# bubbledisplayfrontpack_v01.net
KiCad netlist of a schematic drawn in EAGLE
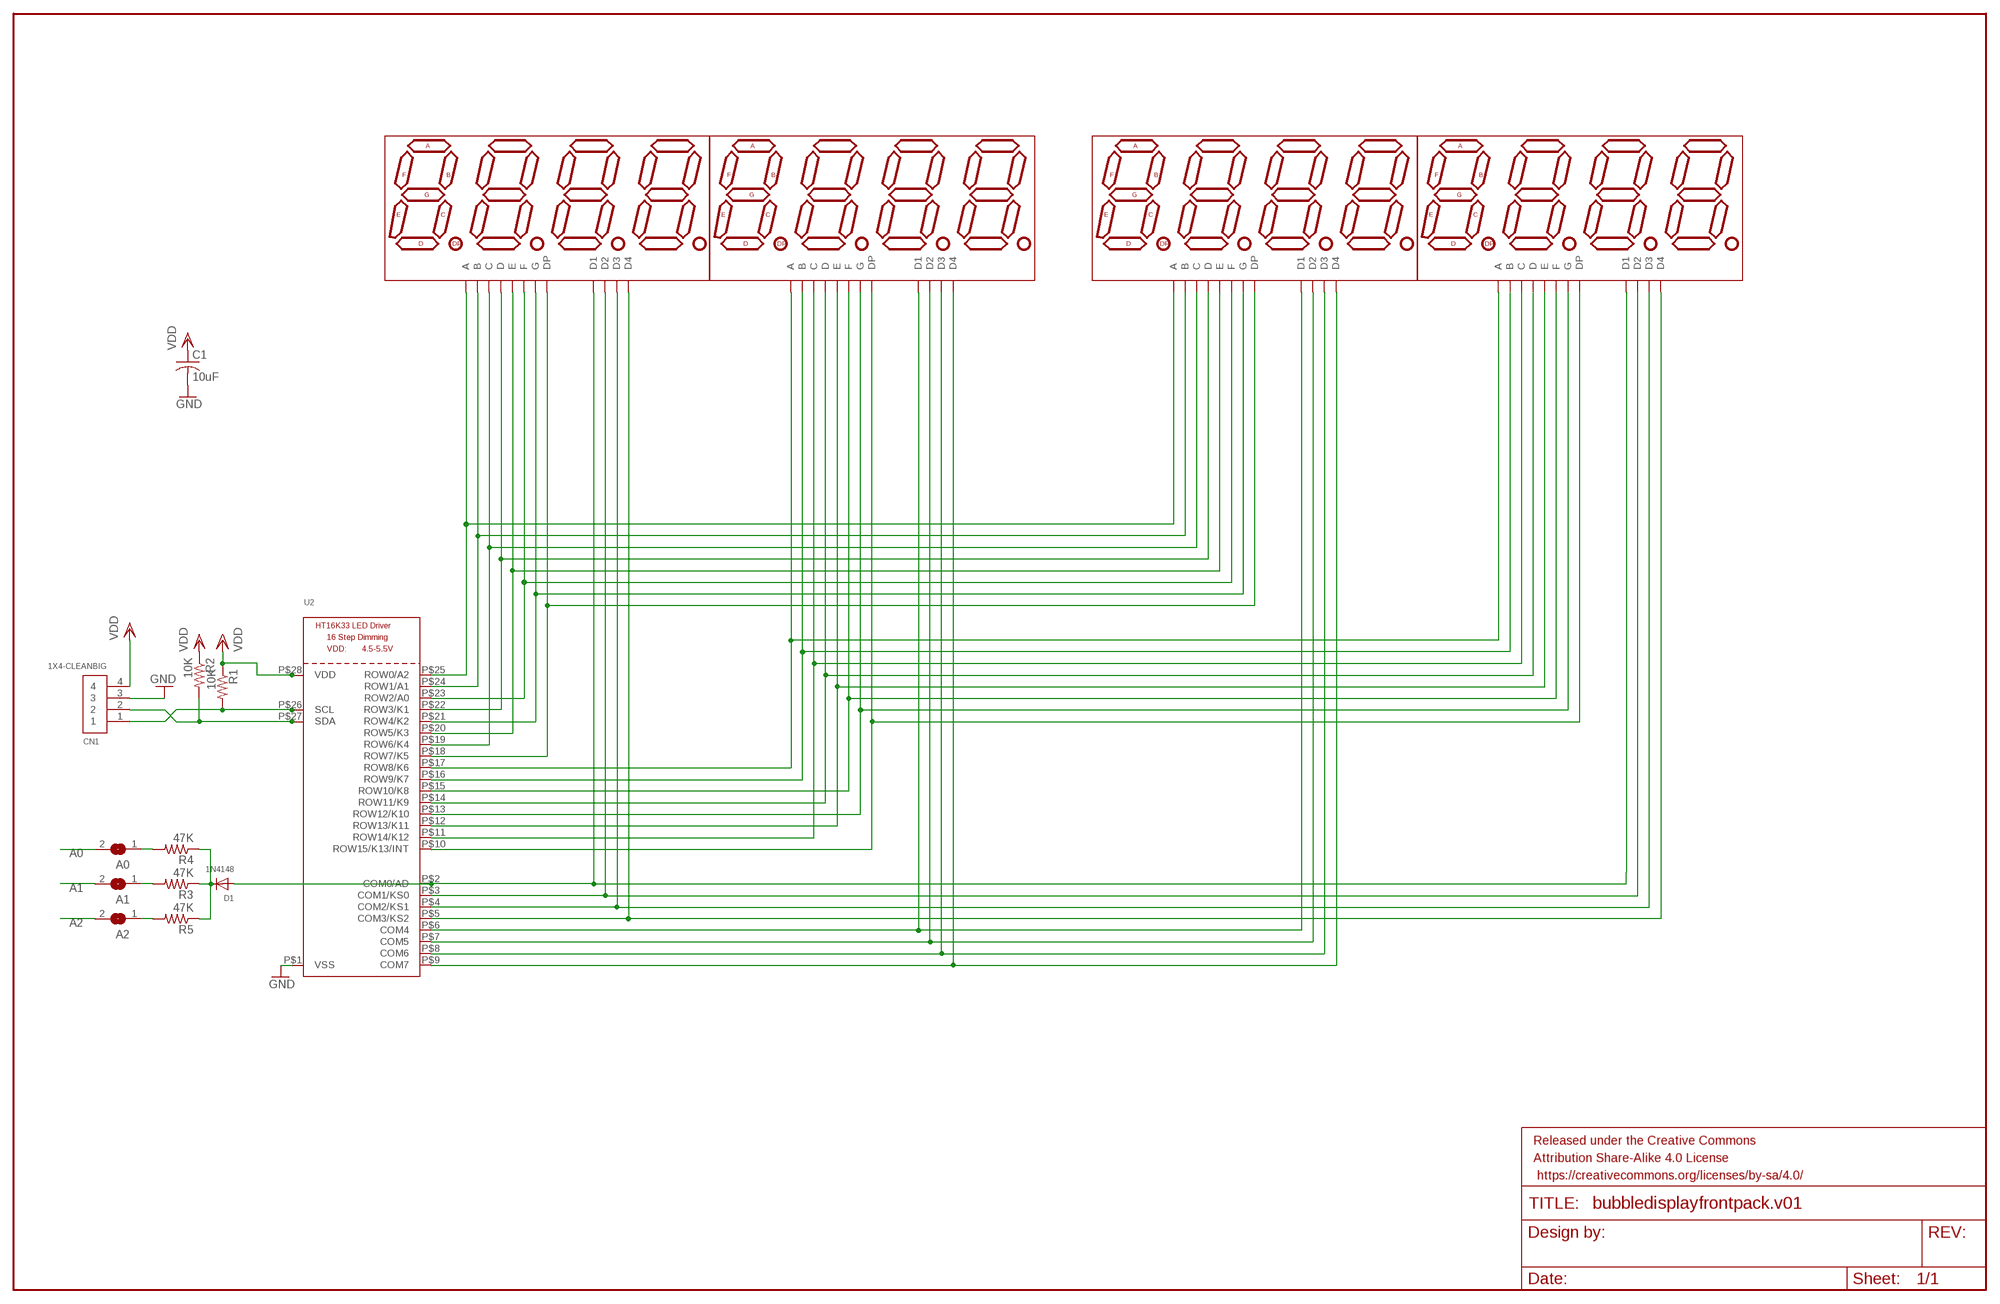
[diagram p0: schematic, sheet 1]

(export (version "E")
  (design (tool "Eeschema 10.0.6"))
  (components
    (comp (ref "A0")
      (value "SOLDERJUMPERREFLOW_NOPASTE")
      (footprint "eagle-import:SOLDERJUMPER_REFLOW_NOPASTE")
      (libsource (lib "eagle-import") (part "SOLDERJUMPERREFLOW_NOPASTE"))
    )
    (comp (ref "A1")
      (value "SOLDERJUMPERREFLOW_NOPASTE")
      (footprint "eagle-import:SOLDERJUMPER_REFLOW_NOPASTE")
      (libsource (lib "eagle-import") (part "SOLDERJUMPERREFLOW_NOPASTE"))
    )
    (comp (ref "A2")
      (value "SOLDERJUMPERREFLOW_NOPASTE")
      (footprint "eagle-import:SOLDERJUMPER_REFLOW_NOPASTE")
      (libsource (lib "eagle-import") (part "SOLDERJUMPERREFLOW_NOPASTE"))
    )
    (comp (ref "C1")
      (value "10uF")
      (footprint "eagle-import:C0805K")
      (libsource (lib "eagle-import") (part "C-USC0805K"))
    )
    (comp (ref "CN1")
      (value "1X4-CLEANBIG")
      (footprint "eagle-import:1X04-CLEANBIG")
      (libsource (lib "eagle-import") (part "1X4-CLEANBIG"))
    )
    (comp (ref "D1")
      (value "1N4148")
      (footprint "eagle-import:SOD-323F")
      (libsource (lib "eagle-import") (part "DIODESOD-323F"))
    )
    (comp (ref "DISPLAY1")
      (value "hp")
      (footprint "eagle-import:DIL12")
      (libsource (lib "eagle-import") (part "7-SEGMENT-4DIGIT-COUNTER-HP-BUBBLE"))
    )
    (comp (ref "DISPLAY2")
      (value "hp")
      (footprint "eagle-import:DIL12")
      (libsource (lib "eagle-import") (part "7-SEGMENT-4DIGIT-COUNTER-HP-BUBBLE"))
    )
    (comp (ref "DISPLAY3")
      (value "hp")
      (footprint "eagle-import:DIL12")
      (libsource (lib "eagle-import") (part "7-SEGMENT-4DIGIT-COUNTER-HP-BUBBLE"))
    )
    (comp (ref "DISPLAY4")
      (value "hp")
      (footprint "eagle-import:DIL12")
      (libsource (lib "eagle-import") (part "7-SEGMENT-4DIGIT-COUNTER-HP-BUBBLE"))
    )
    (comp (ref "FRAME1")
      (value "FRAME-LEDGER")
      (footprint "eagle-import:CREATIVE_COMMONS")
      (libsource (lib "eagle-import") (part "FRAME-LEDGER"))
    )
    (comp (ref "R1")
      (value "10K")
      (footprint "eagle-import:R0805")
      (libsource (lib "eagle-import") (part "R-US_R0805"))
    )
    (comp (ref "R2")
      (value "10K")
      (footprint "eagle-import:R0805")
      (libsource (lib "eagle-import") (part "R-US_R0805"))
    )
    (comp (ref "R3")
      (value "47K")
      (footprint "eagle-import:R0805")
      (libsource (lib "eagle-import") (part "R-US_R0805"))
    )
    (comp (ref "R4")
      (value "47K")
      (footprint "eagle-import:R0805")
      (libsource (lib "eagle-import") (part "R-US_R0805"))
    )
    (comp (ref "R5")
      (value "47K")
      (footprint "eagle-import:R0805")
      (libsource (lib "eagle-import") (part "R-US_R0805"))
    )
    (comp (ref "U2")
      (value "HT16K33_SOP28")
      (footprint "eagle-import:SOP28_300MIL")
      (libsource (lib "eagle-import") (part "HT16K33_SOP28"))
    )
  )
  (nets
    (net (code "1") (name "/A0") (class "Default")
      (node (ref "A0") (pin "2") (pinfunction "2_2") (pintype "passive"))
      (node (ref "DISPLAY1") (pin "9") (pinfunction "F_9") (pintype "bidirectional"))
      (node (ref "DISPLAY3") (pin "9") (pinfunction "F_9") (pintype "bidirectional"))
      (node (ref "U2") (pin "P$23") (pinfunction "ROW2/A0_P$23") (pintype "bidirectional"))
    )
    (net (code "2") (name "/A1") (class "Default")
      (node (ref "A1") (pin "2") (pinfunction "2_2") (pintype "passive"))
      (node (ref "DISPLAY1") (pin "11") (pinfunction "B_11") (pintype "bidirectional"))
      (node (ref "DISPLAY3") (pin "11") (pinfunction "B_11") (pintype "bidirectional"))
      (node (ref "U2") (pin "P$24") (pinfunction "ROW1/A1_P$24") (pintype "bidirectional"))
    )
    (net (code "3") (name "/A2") (class "Default")
      (node (ref "A2") (pin "2") (pinfunction "2_2") (pintype "passive"))
      (node (ref "DISPLAY1") (pin "12") (pinfunction "A_12") (pintype "bidirectional"))
      (node (ref "DISPLAY3") (pin "12") (pinfunction "A_12") (pintype "bidirectional"))
      (node (ref "U2") (pin "P$25") (pinfunction "ROW0/A2_P$25") (pintype "bidirectional"))
    )
    (net (code "4") (name "GND") (class "Default")
      (node (ref "C1") (pin "2") (pinfunction "2_2") (pintype "passive"))
      (node (ref "CN1") (pin "3") (pinfunction "3_3") (pintype "bidirectional"))
      (node (ref "U2") (pin "P$1") (pinfunction "VSS_P$1") (pintype "bidirectional"))
    )
    (net (code "5") (name "Net-(A0-Pad1)") (class "Default")
      (node (ref "A0") (pin "1") (pinfunction "1_1") (pintype "passive"))
      (node (ref "R4") (pin "2") (pinfunction "2_2") (pintype "passive"))
    )
    (net (code "6") (name "Net-(A1-Pad1)") (class "Default")
      (node (ref "A1") (pin "1") (pinfunction "1_1") (pintype "passive"))
      (node (ref "R3") (pin "2") (pinfunction "2_2") (pintype "passive"))
    )
    (net (code "7") (name "Net-(A2-Pad1)") (class "Default")
      (node (ref "A2") (pin "1") (pinfunction "1_1") (pintype "passive"))
      (node (ref "R5") (pin "2") (pinfunction "2_2") (pintype "passive"))
    )
    (net (code "8") (name "Net-(D1-PadC)") (class "Default")
      (node (ref "D1") (pin "C") (pinfunction "C_C") (pintype "passive"))
      (node (ref "R3") (pin "1") (pinfunction "1_1") (pintype "passive"))
      (node (ref "R4") (pin "1") (pinfunction "1_1") (pintype "passive"))
      (node (ref "R5") (pin "1") (pinfunction "1_1") (pintype "passive"))
    )
    (net (code "9") (name "Net-(DISPLAY1-C)") (class "Default")
      (node (ref "DISPLAY1") (pin "3") (pinfunction "C_3") (pintype "bidirectional"))
      (node (ref "DISPLAY3") (pin "3") (pinfunction "C_3") (pintype "bidirectional"))
      (node (ref "U2") (pin "P$19") (pinfunction "ROW6/K4_P$19") (pintype "bidirectional"))
    )
    (net (code "10") (name "Net-(DISPLAY1-D)") (class "Default")
      (node (ref "DISPLAY1") (pin "8") (pinfunction "D_8") (pintype "bidirectional"))
      (node (ref "DISPLAY3") (pin "8") (pinfunction "D_8") (pintype "bidirectional"))
      (node (ref "U2") (pin "P$22") (pinfunction "ROW3/K1_P$22") (pintype "bidirectional"))
    )
    (net (code "11") (name "Net-(DISPLAY1-D1)") (class "Default")
      (node (ref "DISPLAY1") (pin "1") (pinfunction "D1_1") (pintype "bidirectional"))
      (node (ref "DISPLAY4") (pin "1") (pinfunction "D1_1") (pintype "bidirectional"))
      (node (ref "U2") (pin "P$6") (pinfunction "COM4_P$6") (pintype "bidirectional"))
    )
    (net (code "12") (name "Net-(DISPLAY1-D2)") (class "Default")
      (node (ref "DISPLAY1") (pin "10") (pinfunction "D2_10") (pintype "bidirectional"))
      (node (ref "DISPLAY4") (pin "10") (pinfunction "D2_10") (pintype "bidirectional"))
      (node (ref "U2") (pin "P$7") (pinfunction "COM5_P$7") (pintype "bidirectional"))
    )
    (net (code "13") (name "Net-(DISPLAY1-D3)") (class "Default")
      (node (ref "DISPLAY1") (pin "4") (pinfunction "D3_4") (pintype "bidirectional"))
      (node (ref "DISPLAY4") (pin "4") (pinfunction "D3_4") (pintype "bidirectional"))
      (node (ref "U2") (pin "P$8") (pinfunction "COM6_P$8") (pintype "bidirectional"))
    )
    (net (code "14") (name "Net-(DISPLAY1-D4)") (class "Default")
      (node (ref "DISPLAY1") (pin "6") (pinfunction "D4_6") (pintype "bidirectional"))
      (node (ref "DISPLAY4") (pin "6") (pinfunction "D4_6") (pintype "bidirectional"))
      (node (ref "U2") (pin "P$9") (pinfunction "COM7_P$9") (pintype "bidirectional"))
    )
    (net (code "15") (name "Net-(DISPLAY1-DP)") (class "Default")
      (node (ref "DISPLAY1") (pin "5") (pinfunction "DP_5") (pintype "bidirectional"))
      (node (ref "DISPLAY3") (pin "5") (pinfunction "DP_5") (pintype "bidirectional"))
      (node (ref "U2") (pin "P$18") (pinfunction "ROW7/K5_P$18") (pintype "bidirectional"))
    )
    (net (code "16") (name "Net-(DISPLAY1-E)") (class "Default")
      (node (ref "DISPLAY1") (pin "2") (pinfunction "E_2") (pintype "bidirectional"))
      (node (ref "DISPLAY3") (pin "2") (pinfunction "E_2") (pintype "bidirectional"))
      (node (ref "U2") (pin "P$20") (pinfunction "ROW5/K3_P$20") (pintype "bidirectional"))
    )
    (net (code "17") (name "Net-(DISPLAY1-G)") (class "Default")
      (node (ref "DISPLAY1") (pin "7") (pinfunction "G_7") (pintype "bidirectional"))
      (node (ref "DISPLAY3") (pin "7") (pinfunction "G_7") (pintype "bidirectional"))
      (node (ref "U2") (pin "P$21") (pinfunction "ROW4/K2_P$21") (pintype "bidirectional"))
    )
    (net (code "18") (name "Net-(DISPLAY2-A)") (class "Default")
      (node (ref "DISPLAY2") (pin "12") (pinfunction "A_12") (pintype "bidirectional"))
      (node (ref "DISPLAY4") (pin "12") (pinfunction "A_12") (pintype "bidirectional"))
      (node (ref "U2") (pin "P$17") (pinfunction "ROW8/K6_P$17") (pintype "bidirectional"))
    )
    (net (code "19") (name "Net-(DISPLAY2-B)") (class "Default")
      (node (ref "DISPLAY2") (pin "11") (pinfunction "B_11") (pintype "bidirectional"))
      (node (ref "DISPLAY4") (pin "11") (pinfunction "B_11") (pintype "bidirectional"))
      (node (ref "U2") (pin "P$16") (pinfunction "ROW9/K7_P$16") (pintype "bidirectional"))
    )
    (net (code "20") (name "Net-(DISPLAY2-C)") (class "Default")
      (node (ref "DISPLAY2") (pin "3") (pinfunction "C_3") (pintype "bidirectional"))
      (node (ref "DISPLAY4") (pin "3") (pinfunction "C_3") (pintype "bidirectional"))
      (node (ref "U2") (pin "P$11") (pinfunction "ROW14/K12_P$11") (pintype "bidirectional"))
    )
    (net (code "21") (name "Net-(DISPLAY2-D)") (class "Default")
      (node (ref "DISPLAY2") (pin "8") (pinfunction "D_8") (pintype "bidirectional"))
      (node (ref "DISPLAY4") (pin "8") (pinfunction "D_8") (pintype "bidirectional"))
      (node (ref "U2") (pin "P$14") (pinfunction "ROW11/K9_P$14") (pintype "bidirectional"))
    )
    (net (code "22") (name "Net-(DISPLAY2-D1)") (class "Default")
      (node (ref "D1") (pin "A") (pinfunction "A_A") (pintype "passive"))
      (node (ref "DISPLAY2") (pin "1") (pinfunction "D1_1") (pintype "bidirectional"))
      (node (ref "DISPLAY3") (pin "1") (pinfunction "D1_1") (pintype "bidirectional"))
      (node (ref "U2") (pin "P$2") (pinfunction "COM0/AD_P$2") (pintype "bidirectional"))
    )
    (net (code "23") (name "Net-(DISPLAY2-D2)") (class "Default")
      (node (ref "DISPLAY2") (pin "10") (pinfunction "D2_10") (pintype "bidirectional"))
      (node (ref "DISPLAY3") (pin "10") (pinfunction "D2_10") (pintype "bidirectional"))
      (node (ref "U2") (pin "P$3") (pinfunction "COM1/KS0_P$3") (pintype "bidirectional"))
    )
    (net (code "24") (name "Net-(DISPLAY2-D3)") (class "Default")
      (node (ref "DISPLAY2") (pin "4") (pinfunction "D3_4") (pintype "bidirectional"))
      (node (ref "DISPLAY3") (pin "4") (pinfunction "D3_4") (pintype "bidirectional"))
      (node (ref "U2") (pin "P$4") (pinfunction "COM2/KS1_P$4") (pintype "bidirectional"))
    )
    (net (code "25") (name "Net-(DISPLAY2-D4)") (class "Default")
      (node (ref "DISPLAY2") (pin "6") (pinfunction "D4_6") (pintype "bidirectional"))
      (node (ref "DISPLAY3") (pin "6") (pinfunction "D4_6") (pintype "bidirectional"))
      (node (ref "U2") (pin "P$5") (pinfunction "COM3/KS2_P$5") (pintype "bidirectional"))
    )
    (net (code "26") (name "Net-(DISPLAY2-DP)") (class "Default")
      (node (ref "DISPLAY2") (pin "5") (pinfunction "DP_5") (pintype "bidirectional"))
      (node (ref "DISPLAY4") (pin "5") (pinfunction "DP_5") (pintype "bidirectional"))
      (node (ref "U2") (pin "P$10") (pinfunction "ROW15/K13/INT_P$10") (pintype "bidirectional"))
    )
    (net (code "27") (name "Net-(DISPLAY2-E)") (class "Default")
      (node (ref "DISPLAY2") (pin "2") (pinfunction "E_2") (pintype "bidirectional"))
      (node (ref "DISPLAY4") (pin "2") (pinfunction "E_2") (pintype "bidirectional"))
      (node (ref "U2") (pin "P$12") (pinfunction "ROW13/K11_P$12") (pintype "bidirectional"))
    )
    (net (code "28") (name "Net-(DISPLAY2-F)") (class "Default")
      (node (ref "DISPLAY2") (pin "9") (pinfunction "F_9") (pintype "bidirectional"))
      (node (ref "DISPLAY4") (pin "9") (pinfunction "F_9") (pintype "bidirectional"))
      (node (ref "U2") (pin "P$15") (pinfunction "ROW10/K8_P$15") (pintype "bidirectional"))
    )
    (net (code "29") (name "Net-(DISPLAY2-G)") (class "Default")
      (node (ref "DISPLAY2") (pin "7") (pinfunction "G_7") (pintype "bidirectional"))
      (node (ref "DISPLAY4") (pin "7") (pinfunction "G_7") (pintype "bidirectional"))
      (node (ref "U2") (pin "P$13") (pinfunction "ROW12/K10_P$13") (pintype "bidirectional"))
    )
    (net (code "30") (name "Net-(U2-SCL)") (class "Default")
      (node (ref "CN1") (pin "1") (pinfunction "1_1") (pintype "bidirectional"))
      (node (ref "R1") (pin "2") (pinfunction "2_2") (pintype "passive"))
      (node (ref "U2") (pin "P$26") (pinfunction "SCL_P$26") (pintype "bidirectional"))
    )
    (net (code "31") (name "Net-(U2-SDA)") (class "Default")
      (node (ref "CN1") (pin "2") (pinfunction "2_2") (pintype "bidirectional"))
      (node (ref "R2") (pin "2") (pinfunction "2_2") (pintype "passive"))
      (node (ref "U2") (pin "P$27") (pinfunction "SDA_P$27") (pintype "bidirectional"))
    )
    (net (code "32") (name "VDD") (class "Default")
      (node (ref "C1") (pin "1") (pinfunction "1_1") (pintype "passive"))
      (node (ref "CN1") (pin "4") (pinfunction "4_4") (pintype "bidirectional"))
      (node (ref "R1") (pin "1") (pinfunction "1_1") (pintype "passive"))
      (node (ref "R2") (pin "1") (pinfunction "1_1") (pintype "passive"))
      (node (ref "U2") (pin "P$28") (pinfunction "VDD_P$28") (pintype "bidirectional"))
    )
  )
)
